# wemosRx.net
KiCad netlist of a schematic drawn in EAGLE
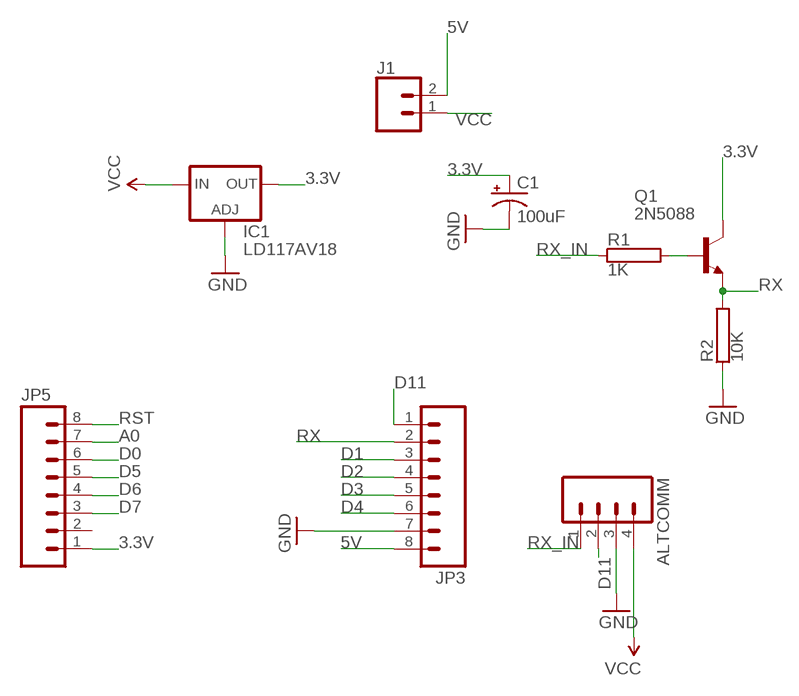
[diagram p0: schematic, sheet 1]

(export (version "E")
  (design (tool "Eeschema 10.0.6"))
  (components
    (comp (ref "ALTCOMM")
      (value "M04LONGPADS")
      (footprint "eagle-import:1X04_LONGPADS@1")
      (libsource (lib "eagle-import") (part "M04LONGPADS"))
    )
    (comp (ref "C1")
      (value "100uF")
      (footprint "eagle-import:CPOL-RADIAL-2.5MM-6.5MM")
      (libsource (lib "eagle-import") (part "100UF-POLAR-RADIAL-2.5MM-25V-20%"))
    )
    (comp (ref "IC1")
      (value "LD117AV18")
      (footprint "eagle-import:TO220L1")
      (libsource (lib "eagle-import") (part "LD117A?V18"))
    )
    (comp (ref "J1")
      (value "CONN_02")
      (footprint "eagle-import:1X02")
      (libsource (lib "eagle-import") (part "CONN_02"))
    )
    (comp (ref "JP3")
      (value "M08LONGPADS")
      (footprint "eagle-import:1X08_LONGPADS")
      (libsource (lib "eagle-import") (part "M08LONGPADS"))
    )
    (comp (ref "JP5")
      (value "M08LONGPADS")
      (footprint "eagle-import:1X08_LONGPADS")
      (libsource (lib "eagle-import") (part "M08LONGPADS"))
    )
    (comp (ref "Q1")
      (value "2N5088")
      (footprint "eagle-import:TO92")
      (libsource (lib "eagle-import") (part "2N5088"))
    )
    (comp (ref "R1")
      (value "1K")
      (footprint "eagle-import:RS1_4")
      (fields (field (name "MF") "OHMITE") (field (name "MPN") "RRS1K0"))
      (libsource (lib "eagle-import") (part "RRS1/4"))
    )
    (comp (ref "R2")
      (value "10K")
      (footprint "eagle-import:RS1_4")
      (fields (field (name "MF") "OHMITE") (field (name "MPN") "RRS1K0"))
      (libsource (lib "eagle-import") (part "RRS1/4"))
    )
  )
  (nets
    (net (code "1") (name "/3.3V") (class "Default")
      (node (ref "C1") (pin "1") (pinfunction "+_1") (pintype "passive"))
      (node (ref "IC1") (pin "2") (pinfunction "OUT_2") (pintype "passive"))
      (node (ref "JP5") (pin "1") (pinfunction "1_1") (pintype "passive"))
      (node (ref "Q1") (pin "1") (pinfunction "C_1") (pintype "passive"))
    )
    (net (code "2") (name "/5V") (class "Default")
      (node (ref "J1") (pin "2") (pinfunction "2_2") (pintype "passive"))
      (node (ref "JP3") (pin "8") (pinfunction "8_8") (pintype "passive"))
    )
    (net (code "3") (name "/A0") (class "Default")
      (node (ref "JP5") (pin "7") (pinfunction "7_7") (pintype "passive"))
    )
    (net (code "4") (name "/D0") (class "Default")
      (node (ref "JP5") (pin "6") (pinfunction "6_6") (pintype "passive"))
    )
    (net (code "5") (name "/D1") (class "Default")
      (node (ref "JP3") (pin "3") (pinfunction "3_3") (pintype "passive"))
    )
    (net (code "6") (name "/D2") (class "Default")
      (node (ref "JP3") (pin "4") (pinfunction "4_4") (pintype "passive"))
    )
    (net (code "7") (name "/D3") (class "Default")
      (node (ref "JP3") (pin "5") (pinfunction "5_5") (pintype "passive"))
    )
    (net (code "8") (name "/D4") (class "Default")
      (node (ref "JP3") (pin "6") (pinfunction "6_6") (pintype "passive"))
    )
    (net (code "9") (name "/D5") (class "Default")
      (node (ref "JP5") (pin "5") (pinfunction "5_5") (pintype "passive"))
    )
    (net (code "10") (name "/D6") (class "Default")
      (node (ref "JP5") (pin "4") (pinfunction "4_4") (pintype "passive"))
    )
    (net (code "11") (name "/D7") (class "Default")
      (node (ref "JP5") (pin "3") (pinfunction "3_3") (pintype "passive"))
    )
    (net (code "12") (name "/D11") (class "Default")
      (node (ref "ALTCOMM") (pin "2") (pinfunction "2_2") (pintype "passive"))
      (node (ref "JP3") (pin "1") (pinfunction "1_1") (pintype "passive"))
    )
    (net (code "13") (name "/RST") (class "Default")
      (node (ref "JP5") (pin "8") (pinfunction "8_8") (pintype "passive"))
    )
    (net (code "14") (name "/RX") (class "Default")
      (node (ref "JP3") (pin "2") (pinfunction "2_2") (pintype "passive"))
      (node (ref "Q1") (pin "3") (pinfunction "E_3") (pintype "passive"))
      (node (ref "R2") (pin "2") (pinfunction "2_2") (pintype "passive"))
    )
    (net (code "15") (name "/RX_IN") (class "Default")
      (node (ref "ALTCOMM") (pin "1") (pinfunction "1_1") (pintype "passive"))
      (node (ref "R1") (pin "1") (pinfunction "1_1") (pintype "passive"))
    )
    (net (code "16") (name "GND") (class "Default")
      (node (ref "ALTCOMM") (pin "3") (pinfunction "3_3") (pintype "passive"))
      (node (ref "C1") (pin "2") (pinfunction "-_2") (pintype "passive"))
      (node (ref "IC1") (pin "1") (pinfunction "ADJ_1") (pintype "input"))
      (node (ref "JP3") (pin "7") (pinfunction "7_7") (pintype "passive"))
      (node (ref "R2") (pin "1") (pinfunction "1_1") (pintype "passive"))
    )
    (net (code "17") (name "Net-(Q1-B)") (class "Default")
      (node (ref "Q1") (pin "2") (pinfunction "B_2") (pintype "passive"))
      (node (ref "R1") (pin "2") (pinfunction "2_2") (pintype "passive"))
    )
    (net (code "18") (name "VCC") (class "Default")
      (node (ref "ALTCOMM") (pin "4") (pinfunction "4_4") (pintype "passive"))
      (node (ref "IC1") (pin "3") (pinfunction "IN_3") (pintype "input"))
      (node (ref "J1") (pin "1") (pinfunction "1_1") (pintype "passive"))
    )
    (net (code "19") (name "unconnected-(JP5-Pad2)") (class "Default")
      (node (ref "JP5") (pin "2") (pinfunction "2_2") (pintype "passive"))
    )
  )
)
